# Sheet1.net
KiCad netlist of a schematic drawn in Altium Designer
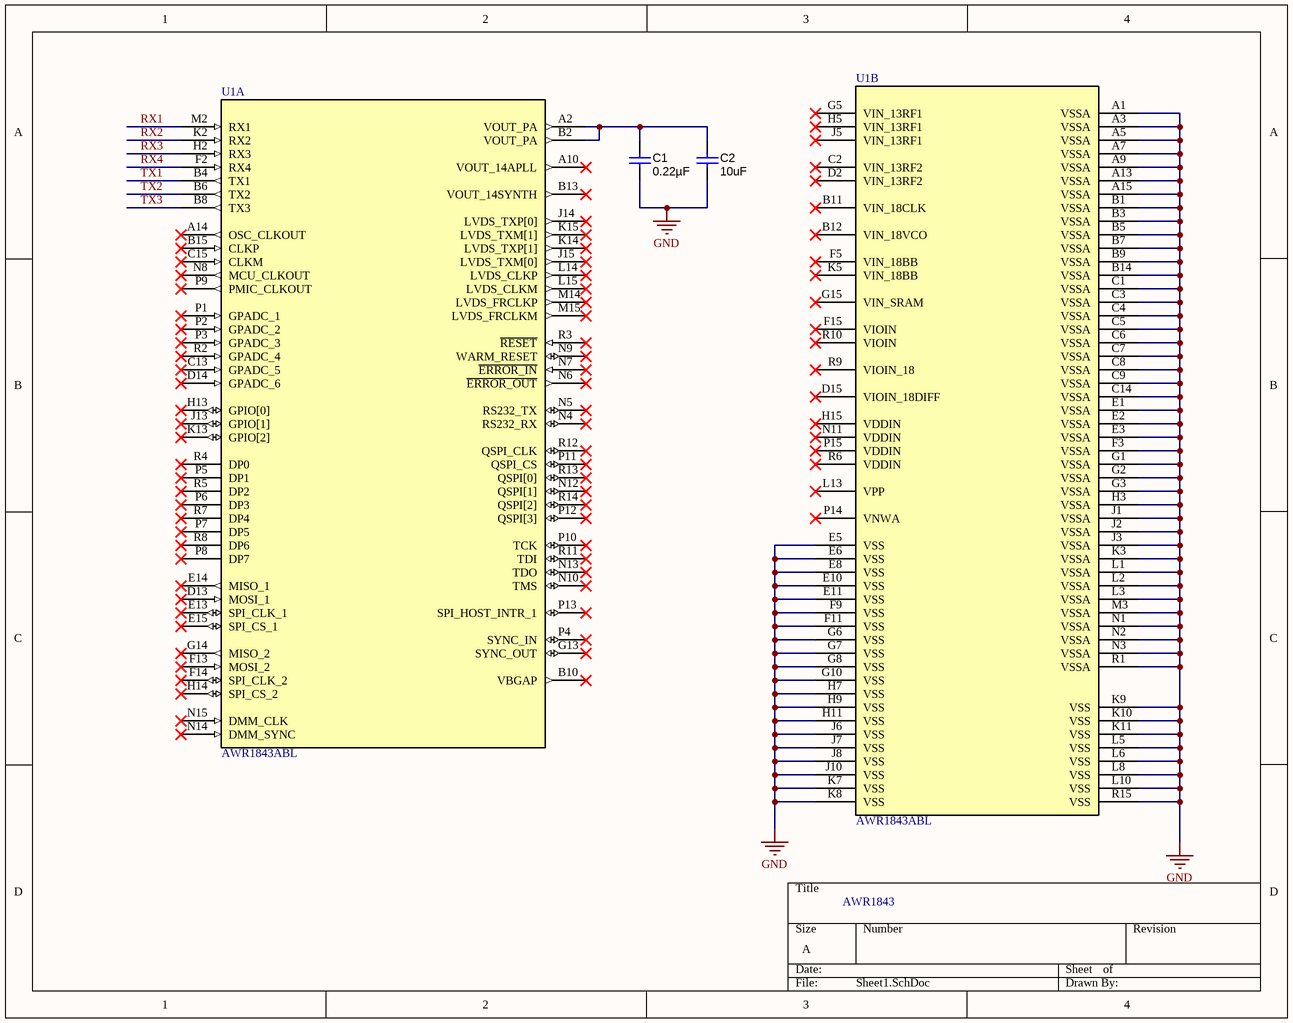
[diagram p0: Sheet1.SchDoc]

(export (version "E")
  (design (tool "Eeschema 10.0.6"))
  (components
    (comp (ref "C1")
      (value "GCM155R71C224KE02D")
      (footprint "0402L")
      (description "CAP, CERM, 0.22 µF, 16 V,+/- 10%, X7R, AEC-Q200 Grade 1, 0402")
      (fields (field (name "MANUFACTURER") "MuRata") (field (name "VALUEDISPLAYED") "0.22µF"))
      (libsource (lib "Schlib1") (part "CMP-0078265-1"))
    )
    (comp (ref "C2")
      (value "GCM21BR71A106KE22L")
      (footprint "0805_HV")
      (description "CAP, CERM, 10 uF, 10 V, +/- 10%, X7R, 0805")
      (fields
        (field (name "MANUFACTURER") "MuRata")
        (field (name "VALUEDISPLAYED") "10uF")
        (field (name "PUBLISHER") "Texas Instruments")
      )
      (libsource (lib "Schlib1") (part "CMP-0008017-2"))
    )
    (comp (ref "U1")
      (value "AWR1843ABL")
      (footprint "ABL0161B")
      (description "AWR1843ABL, ABL0161B (FCBGA-161)")
      (fields (field (name "MANUFACTURER") "Texas Instruments") (field (name "PARTNUMBER") "AWR1843ABL"))
      (libsource (lib "Schlib1") (part "CMP-0078239-1"))
    )
  )
  (nets
    (net (code "1") (name "/RX1") (class "Default")
      (node (ref "U1") (pin "M2") (pinfunction "RX1_M2") (pintype "input"))
    )
    (net (code "2") (name "/RX2") (class "Default")
      (node (ref "U1") (pin "K2") (pinfunction "RX2_K2") (pintype "input"))
    )
    (net (code "3") (name "/RX3") (class "Default")
      (node (ref "U1") (pin "H2") (pinfunction "RX3_H2") (pintype "input"))
    )
    (net (code "4") (name "/RX4") (class "Default")
      (node (ref "U1") (pin "F2") (pinfunction "RX4_F2") (pintype "input"))
    )
    (net (code "5") (name "/TX1") (class "Default")
      (node (ref "U1") (pin "B4") (pinfunction "TX1_B4") (pintype "output"))
    )
    (net (code "6") (name "/TX2") (class "Default")
      (node (ref "U1") (pin "B6") (pinfunction "TX2_B6") (pintype "output"))
    )
    (net (code "7") (name "/TX3") (class "Default")
      (node (ref "U1") (pin "B8") (pinfunction "TX3_B8") (pintype "output"))
    )
    (net (code "8") (name "GND") (class "Default")
      (node (ref "C1") (pin "2") (pinfunction "2_2") (pintype "passive"))
      (node (ref "C2") (pin "2") (pinfunction "2_2") (pintype "passive"))
      (node (ref "U1") (pin "A1") (pinfunction "VSSA_A1") (pintype "power_in"))
      (node (ref "U1") (pin "A13") (pinfunction "VSSA_A13") (pintype "power_in"))
      (node (ref "U1") (pin "A15") (pinfunction "VSSA_A15") (pintype "power_in"))
      (node (ref "U1") (pin "A3") (pinfunction "VSSA_A3") (pintype "power_in"))
      (node (ref "U1") (pin "A5") (pinfunction "VSSA_A5") (pintype "power_in"))
      (node (ref "U1") (pin "A7") (pinfunction "VSSA_A7") (pintype "power_in"))
      (node (ref "U1") (pin "A9") (pinfunction "VSSA_A9") (pintype "power_in"))
      (node (ref "U1") (pin "B1") (pinfunction "VSSA_B1") (pintype "power_in"))
      (node (ref "U1") (pin "B14") (pinfunction "VSSA_B14") (pintype "power_in"))
      (node (ref "U1") (pin "B3") (pinfunction "VSSA_B3") (pintype "power_in"))
      (node (ref "U1") (pin "B5") (pinfunction "VSSA_B5") (pintype "power_in"))
      (node (ref "U1") (pin "B7") (pinfunction "VSSA_B7") (pintype "power_in"))
      (node (ref "U1") (pin "B9") (pinfunction "VSSA_B9") (pintype "power_in"))
      (node (ref "U1") (pin "C1") (pinfunction "VSSA_C1") (pintype "power_in"))
      (node (ref "U1") (pin "C14") (pinfunction "VSSA_C14") (pintype "power_in"))
      (node (ref "U1") (pin "C3") (pinfunction "VSSA_C3") (pintype "power_in"))
      (node (ref "U1") (pin "C4") (pinfunction "VSSA_C4") (pintype "power_in"))
      (node (ref "U1") (pin "C5") (pinfunction "VSSA_C5") (pintype "power_in"))
      (node (ref "U1") (pin "C6") (pinfunction "VSSA_C6") (pintype "power_in"))
      (node (ref "U1") (pin "C7") (pinfunction "VSSA_C7") (pintype "power_in"))
      (node (ref "U1") (pin "C8") (pinfunction "VSSA_C8") (pintype "power_in"))
      (node (ref "U1") (pin "C9") (pinfunction "VSSA_C9") (pintype "power_in"))
      (node (ref "U1") (pin "E1") (pinfunction "VSSA_E1") (pintype "power_in"))
      (node (ref "U1") (pin "E10") (pinfunction "VSS_E10") (pintype "power_in"))
      (node (ref "U1") (pin "E11") (pinfunction "VSS_E11") (pintype "power_in"))
      (node (ref "U1") (pin "E2") (pinfunction "VSSA_E2") (pintype "power_in"))
      (node (ref "U1") (pin "E3") (pinfunction "VSSA_E3") (pintype "power_in"))
      (node (ref "U1") (pin "E5") (pinfunction "VSS_E5") (pintype "power_in"))
      (node (ref "U1") (pin "E6") (pinfunction "VSS_E6") (pintype "power_in"))
      (node (ref "U1") (pin "E8") (pinfunction "VSS_E8") (pintype "power_in"))
      (node (ref "U1") (pin "F11") (pinfunction "VSS_F11") (pintype "power_in"))
      (node (ref "U1") (pin "F3") (pinfunction "VSSA_F3") (pintype "power_in"))
      (node (ref "U1") (pin "F9") (pinfunction "VSS_F9") (pintype "power_in"))
      (node (ref "U1") (pin "G1") (pinfunction "VSSA_G1") (pintype "power_in"))
      (node (ref "U1") (pin "G10") (pinfunction "VSS_G10") (pintype "power_in"))
      (node (ref "U1") (pin "G2") (pinfunction "VSSA_G2") (pintype "power_in"))
      (node (ref "U1") (pin "G3") (pinfunction "VSSA_G3") (pintype "power_in"))
      (node (ref "U1") (pin "G6") (pinfunction "VSS_G6") (pintype "power_in"))
      (node (ref "U1") (pin "G7") (pinfunction "VSS_G7") (pintype "power_in"))
      (node (ref "U1") (pin "G8") (pinfunction "VSS_G8") (pintype "power_in"))
      (node (ref "U1") (pin "H11") (pinfunction "VSS_H11") (pintype "power_in"))
      (node (ref "U1") (pin "H3") (pinfunction "VSSA_H3") (pintype "power_in"))
      (node (ref "U1") (pin "H7") (pinfunction "VSS_H7") (pintype "power_in"))
      (node (ref "U1") (pin "H9") (pinfunction "VSS_H9") (pintype "power_in"))
      (node (ref "U1") (pin "J1") (pinfunction "VSSA_J1") (pintype "power_in"))
      (node (ref "U1") (pin "J10") (pinfunction "VSS_J10") (pintype "power_in"))
      (node (ref "U1") (pin "J2") (pinfunction "VSSA_J2") (pintype "power_in"))
      (node (ref "U1") (pin "J3") (pinfunction "VSSA_J3") (pintype "power_in"))
      (node (ref "U1") (pin "J6") (pinfunction "VSS_J6") (pintype "power_in"))
      (node (ref "U1") (pin "J7") (pinfunction "VSS_J7") (pintype "power_in"))
      (node (ref "U1") (pin "J8") (pinfunction "VSS_J8") (pintype "power_in"))
      (node (ref "U1") (pin "K10") (pinfunction "VSS_K10") (pintype "power_in"))
      (node (ref "U1") (pin "K11") (pinfunction "VSS_K11") (pintype "power_in"))
      (node (ref "U1") (pin "K3") (pinfunction "VSSA_K3") (pintype "power_in"))
      (node (ref "U1") (pin "K7") (pinfunction "VSS_K7") (pintype "power_in"))
      (node (ref "U1") (pin "K8") (pinfunction "VSS_K8") (pintype "power_in"))
      (node (ref "U1") (pin "K9") (pinfunction "VSS_K9") (pintype "power_in"))
      (node (ref "U1") (pin "L1") (pinfunction "VSSA_L1") (pintype "power_in"))
      (node (ref "U1") (pin "L10") (pinfunction "VSS_L10") (pintype "power_in"))
      (node (ref "U1") (pin "L2") (pinfunction "VSSA_L2") (pintype "power_in"))
      (node (ref "U1") (pin "L3") (pinfunction "VSSA_L3") (pintype "power_in"))
      (node (ref "U1") (pin "L5") (pinfunction "VSS_L5") (pintype "power_in"))
      (node (ref "U1") (pin "L6") (pinfunction "VSS_L6") (pintype "power_in"))
      (node (ref "U1") (pin "L8") (pinfunction "VSS_L8") (pintype "power_in"))
      (node (ref "U1") (pin "M3") (pinfunction "VSSA_M3") (pintype "power_in"))
      (node (ref "U1") (pin "N1") (pinfunction "VSSA_N1") (pintype "power_in"))
      (node (ref "U1") (pin "N2") (pinfunction "VSSA_N2") (pintype "power_in"))
      (node (ref "U1") (pin "N3") (pinfunction "VSSA_N3") (pintype "power_in"))
      (node (ref "U1") (pin "R1") (pinfunction "VSSA_R1") (pintype "power_in"))
      (node (ref "U1") (pin "R15") (pinfunction "VSS_R15") (pintype "power_in"))
    )
    (net (code "9") (name "Net-(C1-Pad1)") (class "Default")
      (node (ref "C1") (pin "1") (pinfunction "1_1") (pintype "passive"))
      (node (ref "C2") (pin "1") (pinfunction "1_1") (pintype "passive"))
      (node (ref "U1") (pin "A2") (pinfunction "VOUT_PA_A2") (pintype "output"))
      (node (ref "U1") (pin "B2") (pinfunction "VOUT_PA_B2") (pintype "output"))
    )
    (net (code "10") (name "unconnected-(U1A-CLKM-PadC15)") (class "Default")
      (node (ref "U1") (pin "C15") (pinfunction "CLKM_C15") (pintype "input+no_connect"))
    )
    (net (code "11") (name "unconnected-(U1A-CLKP-PadB15)") (class "Default")
      (node (ref "U1") (pin "B15") (pinfunction "CLKP_B15") (pintype "input+no_connect"))
    )
    (net (code "12") (name "unconnected-(U1A-DMM_CLK-PadN15)") (class "Default")
      (node (ref "U1") (pin "N15") (pinfunction "DMM_CLK_N15") (pintype "input+no_connect"))
    )
    (net (code "13") (name "unconnected-(U1A-DMM_SYNC-PadN14)") (class "Default")
      (node (ref "U1") (pin "N14") (pinfunction "DMM_SYNC_N14") (pintype "input+no_connect"))
    )
    (net (code "14") (name "unconnected-(U1A-DP0-PadR4)") (class "Default")
      (node (ref "U1") (pin "R4") (pinfunction "DP0_R4") (pintype "passive+no_connect"))
    )
    (net (code "15") (name "unconnected-(U1A-DP1-PadP5)") (class "Default")
      (node (ref "U1") (pin "P5") (pinfunction "DP1_P5") (pintype "passive+no_connect"))
    )
    (net (code "16") (name "unconnected-(U1A-DP2-PadR5)") (class "Default")
      (node (ref "U1") (pin "R5") (pinfunction "DP2_R5") (pintype "passive+no_connect"))
    )
    (net (code "17") (name "unconnected-(U1A-DP3-PadP6)") (class "Default")
      (node (ref "U1") (pin "P6") (pinfunction "DP3_P6") (pintype "passive+no_connect"))
    )
    (net (code "18") (name "unconnected-(U1A-DP4-PadR7)") (class "Default")
      (node (ref "U1") (pin "R7") (pinfunction "DP4_R7") (pintype "passive+no_connect"))
    )
    (net (code "19") (name "unconnected-(U1A-DP5-PadP7)") (class "Default")
      (node (ref "U1") (pin "P7") (pinfunction "DP5_P7") (pintype "passive+no_connect"))
    )
    (net (code "20") (name "unconnected-(U1A-DP6-PadR8)") (class "Default")
      (node (ref "U1") (pin "R8") (pinfunction "DP6_R8") (pintype "passive+no_connect"))
    )
    (net (code "21") (name "unconnected-(U1A-DP7-PadP8)") (class "Default")
      (node (ref "U1") (pin "P8") (pinfunction "DP7_P8") (pintype "passive+no_connect"))
    )
    (net (code "22") (name "unconnected-(U1A-ERROR_IN-PadN7)") (class "Default")
      (node (ref "U1") (pin "N7") (pinfunction "ERROR_IN_N7") (pintype "input+no_connect"))
    )
    (net (code "23") (name "unconnected-(U1A-ERROR_OUT-PadN6)") (class "Default")
      (node (ref "U1") (pin "N6") (pinfunction "ERROR_OUT_N6") (pintype "output+no_connect"))
    )
    (net (code "24") (name "unconnected-(U1A-GPADC_1-PadP1)") (class "Default")
      (node (ref "U1") (pin "P1") (pinfunction "GPADC_1_P1") (pintype "input+no_connect"))
    )
    (net (code "25") (name "unconnected-(U1A-GPADC_2-PadP2)") (class "Default")
      (node (ref "U1") (pin "P2") (pinfunction "GPADC_2_P2") (pintype "input+no_connect"))
    )
    (net (code "26") (name "unconnected-(U1A-GPADC_3-PadP3)") (class "Default")
      (node (ref "U1") (pin "P3") (pinfunction "GPADC_3_P3") (pintype "input+no_connect"))
    )
    (net (code "27") (name "unconnected-(U1A-GPADC_4-PadR2)") (class "Default")
      (node (ref "U1") (pin "R2") (pinfunction "GPADC_4_R2") (pintype "input+no_connect"))
    )
    (net (code "28") (name "unconnected-(U1A-GPADC_5-PadC13)") (class "Default")
      (node (ref "U1") (pin "C13") (pinfunction "GPADC_5_C13") (pintype "input+no_connect"))
    )
    (net (code "29") (name "unconnected-(U1A-GPADC_6-PadD14)") (class "Default")
      (node (ref "U1") (pin "D14") (pinfunction "GPADC_6_D14") (pintype "input+no_connect"))
    )
    (net (code "30") (name "unconnected-(U1A-GPIO[0]-PadH13)") (class "Default")
      (node (ref "U1") (pin "H13") (pinfunction "GPIO[0]_H13") (pintype "bidirectional+no_connect"))
    )
    (net (code "31") (name "unconnected-(U1A-GPIO[1]-PadJ13)") (class "Default")
      (node (ref "U1") (pin "J13") (pinfunction "GPIO[1]_J13") (pintype "bidirectional+no_connect"))
    )
    (net (code "32") (name "unconnected-(U1A-GPIO[2]-PadK13)") (class "Default")
      (node (ref "U1") (pin "K13") (pinfunction "GPIO[2]_K13") (pintype "bidirectional+no_connect"))
    )
    (net (code "33") (name "unconnected-(U1A-LVDS_CLKM-PadL15)") (class "Default")
      (node (ref "U1") (pin "L15") (pinfunction "LVDS_CLKM_L15") (pintype "output+no_connect"))
    )
    (net (code "34") (name "unconnected-(U1A-LVDS_CLKP-PadL14)") (class "Default")
      (node (ref "U1") (pin "L14") (pinfunction "LVDS_CLKP_L14") (pintype "output+no_connect"))
    )
    (net (code "35") (name "unconnected-(U1A-LVDS_FRCLKM-PadM15)") (class "Default")
      (node (ref "U1") (pin "M15") (pinfunction "LVDS_FRCLKM_M15") (pintype "output+no_connect"))
    )
    (net (code "36") (name "unconnected-(U1A-LVDS_FRCLKP-PadM14)") (class "Default")
      (node (ref "U1") (pin "M14") (pinfunction "LVDS_FRCLKP_M14") (pintype "output+no_connect"))
    )
    (net (code "37") (name "unconnected-(U1A-LVDS_TXM[0]-PadJ15)") (class "Default")
      (node (ref "U1") (pin "J15") (pinfunction "LVDS_TXM[0]_J15") (pintype "output+no_connect"))
    )
    (net (code "38") (name "unconnected-(U1A-LVDS_TXM[1]-PadK15)") (class "Default")
      (node (ref "U1") (pin "K15") (pinfunction "LVDS_TXM[1]_K15") (pintype "output+no_connect"))
    )
    (net (code "39") (name "unconnected-(U1A-LVDS_TXP[0]-PadJ14)") (class "Default")
      (node (ref "U1") (pin "J14") (pinfunction "LVDS_TXP[0]_J14") (pintype "output+no_connect"))
    )
    (net (code "40") (name "unconnected-(U1A-LVDS_TXP[1]-PadK14)") (class "Default")
      (node (ref "U1") (pin "K14") (pinfunction "LVDS_TXP[1]_K14") (pintype "output+no_connect"))
    )
    (net (code "41") (name "unconnected-(U1A-MCU_CLKOUT-PadN8)") (class "Default")
      (node (ref "U1") (pin "N8") (pinfunction "MCU_CLKOUT_N8") (pintype "output+no_connect"))
    )
    (net (code "42") (name "unconnected-(U1A-MISO_1-PadE14)") (class "Default")
      (node (ref "U1") (pin "E14") (pinfunction "MISO_1_E14") (pintype "output+no_connect"))
    )
    (net (code "43") (name "unconnected-(U1A-MISO_2-PadG14)") (class "Default")
      (node (ref "U1") (pin "G14") (pinfunction "MISO_2_G14") (pintype "output+no_connect"))
    )
    (net (code "44") (name "unconnected-(U1A-MOSI_1-PadD13)") (class "Default")
      (node (ref "U1") (pin "D13") (pinfunction "MOSI_1_D13") (pintype "input+no_connect"))
    )
    (net (code "45") (name "unconnected-(U1A-MOSI_2-PadF13)") (class "Default")
      (node (ref "U1") (pin "F13") (pinfunction "MOSI_2_F13") (pintype "input+no_connect"))
    )
    (net (code "46") (name "unconnected-(U1A-OSC_CLKOUT-PadA14)") (class "Default")
      (node (ref "U1") (pin "A14") (pinfunction "OSC_CLKOUT_A14") (pintype "output+no_connect"))
    )
    (net (code "47") (name "unconnected-(U1A-PMIC_CLKOUT-PadP9)") (class "Default")
      (node (ref "U1") (pin "P9") (pinfunction "PMIC_CLKOUT_P9") (pintype "output+no_connect"))
    )
    (net (code "48") (name "unconnected-(U1A-QSPI[0]-PadR13)") (class "Default")
      (node (ref "U1") (pin "R13") (pinfunction "QSPI[0]_R13") (pintype "bidirectional+no_connect"))
    )
    (net (code "49") (name "unconnected-(U1A-QSPI[1]-PadN12)") (class "Default")
      (node (ref "U1") (pin "N12") (pinfunction "QSPI[1]_N12") (pintype "bidirectional+no_connect"))
    )
    (net (code "50") (name "unconnected-(U1A-QSPI[2]-PadR14)") (class "Default")
      (node (ref "U1") (pin "R14") (pinfunction "QSPI[2]_R14") (pintype "bidirectional+no_connect"))
    )
    (net (code "51") (name "unconnected-(U1A-QSPI[3]-PadP12)") (class "Default")
      (node (ref "U1") (pin "P12") (pinfunction "QSPI[3]_P12") (pintype "bidirectional+no_connect"))
    )
    (net (code "52") (name "unconnected-(U1A-QSPI_CLK-PadR12)") (class "Default")
      (node (ref "U1") (pin "R12") (pinfunction "QSPI_CLK_R12") (pintype "bidirectional+no_connect"))
    )
    (net (code "53") (name "unconnected-(U1A-QSPI_CS-PadP11)") (class "Default")
      (node (ref "U1") (pin "P11") (pinfunction "QSPI_CS_P11") (pintype "bidirectional+no_connect"))
    )
    (net (code "54") (name "unconnected-(U1A-RESET-PadR3)") (class "Default")
      (node (ref "U1") (pin "R3") (pinfunction "RESET_R3") (pintype "input+no_connect"))
    )
    (net (code "55") (name "unconnected-(U1A-RS232_RX-PadN4)") (class "Default")
      (node (ref "U1") (pin "N4") (pinfunction "RS232_RX_N4") (pintype "bidirectional+no_connect"))
    )
    (net (code "56") (name "unconnected-(U1A-RS232_TX-PadN5)") (class "Default")
      (node (ref "U1") (pin "N5") (pinfunction "RS232_TX_N5") (pintype "bidirectional+no_connect"))
    )
    (net (code "57") (name "unconnected-(U1A-SPI_CLK_1-PadE13)") (class "Default")
      (node (ref "U1") (pin "E13") (pinfunction "SPI_CLK_1_E13") (pintype "bidirectional+no_connect"))
    )
    (net (code "58") (name "unconnected-(U1A-SPI_CLK_2-PadF14)") (class "Default")
      (node (ref "U1") (pin "F14") (pinfunction "SPI_CLK_2_F14") (pintype "bidirectional+no_connect"))
    )
    (net (code "59") (name "unconnected-(U1A-SPI_CS_1-PadE15)") (class "Default")
      (node (ref "U1") (pin "E15") (pinfunction "SPI_CS_1_E15") (pintype "bidirectional+no_connect"))
    )
    (net (code "60") (name "unconnected-(U1A-SPI_CS_2-PadH14)") (class "Default")
      (node (ref "U1") (pin "H14") (pinfunction "SPI_CS_2_H14") (pintype "bidirectional+no_connect"))
    )
    (net (code "61") (name "unconnected-(U1A-SPI_HOST_INTR_1-PadP13)") (class "Default")
      (node (ref "U1") (pin "P13") (pinfunction "SPI_HOST_INTR_1_P13") (pintype "bidirectional+no_connect"))
    )
    (net (code "62") (name "unconnected-(U1A-SYNC_IN-PadP4)") (class "Default")
      (node (ref "U1") (pin "P4") (pinfunction "SYNC_IN_P4") (pintype "bidirectional+no_connect"))
    )
    (net (code "63") (name "unconnected-(U1A-SYNC_OUT-PadG13)") (class "Default")
      (node (ref "U1") (pin "G13") (pinfunction "SYNC_OUT_G13") (pintype "bidirectional+no_connect"))
    )
    (net (code "64") (name "unconnected-(U1A-TCK-PadP10)") (class "Default")
      (node (ref "U1") (pin "P10") (pinfunction "TCK_P10") (pintype "bidirectional+no_connect"))
    )
    (net (code "65") (name "unconnected-(U1A-TDI-PadR11)") (class "Default")
      (node (ref "U1") (pin "R11") (pinfunction "TDI_R11") (pintype "bidirectional+no_connect"))
    )
    (net (code "66") (name "unconnected-(U1A-TDO-PadN13)") (class "Default")
      (node (ref "U1") (pin "N13") (pinfunction "TDO_N13") (pintype "bidirectional+no_connect"))
    )
    (net (code "67") (name "unconnected-(U1A-TMS-PadN10)") (class "Default")
      (node (ref "U1") (pin "N10") (pinfunction "TMS_N10") (pintype "bidirectional+no_connect"))
    )
    (net (code "68") (name "unconnected-(U1A-VBGAP-PadB10)") (class "Default")
      (node (ref "U1") (pin "B10") (pinfunction "VBGAP_B10") (pintype "output+no_connect"))
    )
    (net (code "69") (name "unconnected-(U1A-VOUT_14APLL-PadA10)") (class "Default")
      (node (ref "U1") (pin "A10") (pinfunction "VOUT_14APLL_A10") (pintype "output+no_connect"))
    )
    (net (code "70") (name "unconnected-(U1A-VOUT_14SYNTH-PadB13)") (class "Default")
      (node (ref "U1") (pin "B13") (pinfunction "VOUT_14SYNTH_B13") (pintype "output+no_connect"))
    )
    (net (code "71") (name "unconnected-(U1A-WARM_RESET-PadN9)") (class "Default")
      (node (ref "U1") (pin "N9") (pinfunction "WARM_RESET_N9") (pintype "bidirectional+no_connect"))
    )
    (net (code "72") (name "unconnected-(U1B-VDDIN-PadH15)") (class "Default")
      (node (ref "U1") (pin "H15") (pinfunction "VDDIN_H15") (pintype "power_in+no_connect"))
    )
    (net (code "73") (name "unconnected-(U1B-VDDIN-PadN11)") (class "Default")
      (node (ref "U1") (pin "N11") (pinfunction "VDDIN_N11") (pintype "power_in+no_connect"))
    )
    (net (code "74") (name "unconnected-(U1B-VDDIN-PadP15)") (class "Default")
      (node (ref "U1") (pin "P15") (pinfunction "VDDIN_P15") (pintype "power_in+no_connect"))
    )
    (net (code "75") (name "unconnected-(U1B-VDDIN-PadR6)") (class "Default")
      (node (ref "U1") (pin "R6") (pinfunction "VDDIN_R6") (pintype "power_in+no_connect"))
    )
    (net (code "76") (name "unconnected-(U1B-VIN_13RF1-PadG5)") (class "Default")
      (node (ref "U1") (pin "G5") (pinfunction "VIN_13RF1_G5") (pintype "power_in+no_connect"))
    )
    (net (code "77") (name "unconnected-(U1B-VIN_13RF1-PadH5)") (class "Default")
      (node (ref "U1") (pin "H5") (pinfunction "VIN_13RF1_H5") (pintype "power_in+no_connect"))
    )
    (net (code "78") (name "unconnected-(U1B-VIN_13RF1-PadJ5)") (class "Default")
      (node (ref "U1") (pin "J5") (pinfunction "VIN_13RF1_J5") (pintype "power_in+no_connect"))
    )
    (net (code "79") (name "unconnected-(U1B-VIN_13RF2-PadC2)") (class "Default")
      (node (ref "U1") (pin "C2") (pinfunction "VIN_13RF2_C2") (pintype "power_in+no_connect"))
    )
    (net (code "80") (name "unconnected-(U1B-VIN_13RF2-PadD2)") (class "Default")
      (node (ref "U1") (pin "D2") (pinfunction "VIN_13RF2_D2") (pintype "power_in+no_connect"))
    )
    (net (code "81") (name "unconnected-(U1B-VIN_18BB-PadF5)") (class "Default")
      (node (ref "U1") (pin "F5") (pinfunction "VIN_18BB_F5") (pintype "power_in+no_connect"))
    )
    (net (code "82") (name "unconnected-(U1B-VIN_18BB-PadK5)") (class "Default")
      (node (ref "U1") (pin "K5") (pinfunction "VIN_18BB_K5") (pintype "power_in+no_connect"))
    )
    (net (code "83") (name "unconnected-(U1B-VIN_18CLK-PadB11)") (class "Default")
      (node (ref "U1") (pin "B11") (pinfunction "VIN_18CLK_B11") (pintype "power_in+no_connect"))
    )
    (net (code "84") (name "unconnected-(U1B-VIN_18VCO-PadB12)") (class "Default")
      (node (ref "U1") (pin "B12") (pinfunction "VIN_18VCO_B12") (pintype "power_in+no_connect"))
    )
    (net (code "85") (name "unconnected-(U1B-VIN_SRAM-PadG15)") (class "Default")
      (node (ref "U1") (pin "G15") (pinfunction "VIN_SRAM_G15") (pintype "power_in+no_connect"))
    )
    (net (code "86") (name "unconnected-(U1B-VIOIN-PadF15)") (class "Default")
      (node (ref "U1") (pin "F15") (pinfunction "VIOIN_F15") (pintype "power_in+no_connect"))
    )
    (net (code "87") (name "unconnected-(U1B-VIOIN-PadR10)") (class "Default")
      (node (ref "U1") (pin "R10") (pinfunction "VIOIN_R10") (pintype "power_in+no_connect"))
    )
    (net (code "88") (name "unconnected-(U1B-VIOIN_18-PadR9)") (class "Default")
      (node (ref "U1") (pin "R9") (pinfunction "VIOIN_18_R9") (pintype "power_in+no_connect"))
    )
    (net (code "89") (name "unconnected-(U1B-VIOIN_18DIFF-PadD15)") (class "Default")
      (node (ref "U1") (pin "D15") (pinfunction "VIOIN_18DIFF_D15") (pintype "power_in+no_connect"))
    )
    (net (code "90") (name "unconnected-(U1B-VNWA-PadP14)") (class "Default")
      (node (ref "U1") (pin "P14") (pinfunction "VNWA_P14") (pintype "power_in+no_connect"))
    )
    (net (code "91") (name "unconnected-(U1B-VPP-PadL13)") (class "Default")
      (node (ref "U1") (pin "L13") (pinfunction "VPP_L13") (pintype "power_in+no_connect"))
    )
  )
)
